# targetboard_v1.net
KiCad netlist of a schematic drawn in EAGLE
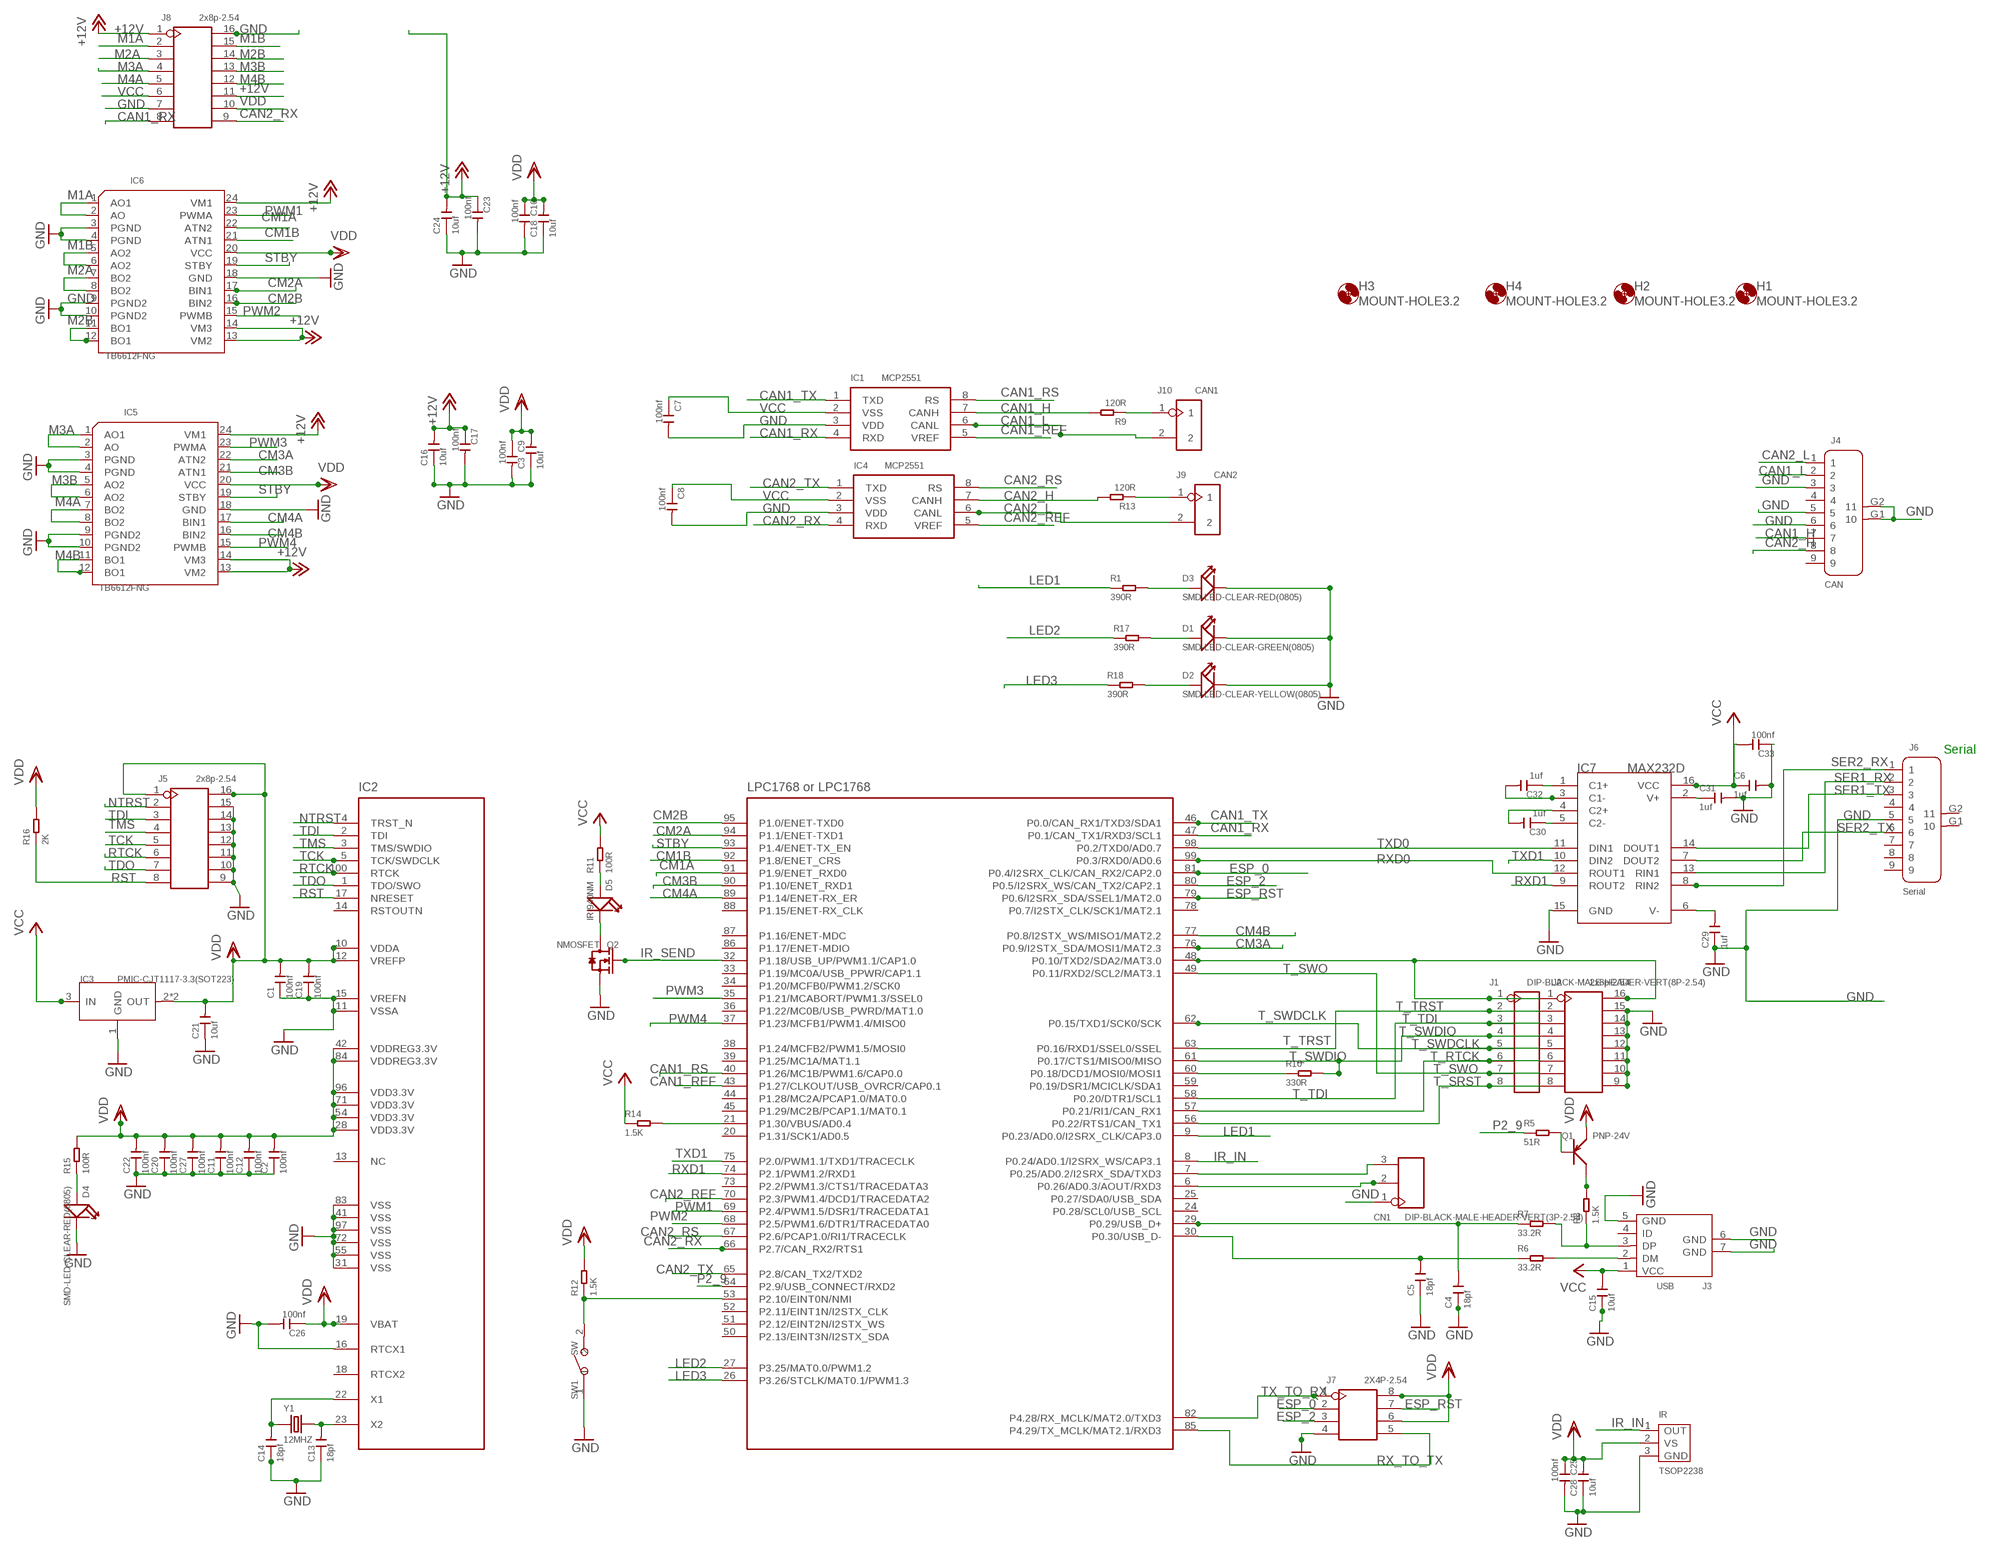
[diagram p0: schematic, sheet 1]

(export (version "E")
  (design (tool "Eeschema 10.0.6"))
  (components
    (comp (ref "C1")
      (value "100nf")
      (footprint "eagle-import:C0805")
      (fields (field (name "MPN") "CC0805KRX7R9BB104"))
      (libsource (lib "eagle-import") (part "CERAMIC-100NF-50V-10%-X7R(0805)"))
    )
    (comp (ref "C2")
      (value "100nf")
      (footprint "eagle-import:C0805")
      (fields (field (name "MPN") "CC0805KRX7R9BB104"))
      (libsource (lib "eagle-import") (part "CERAMIC-100NF-50V-10%-X7R(0805)"))
    )
    (comp (ref "C3")
      (value "10uf")
      (footprint "eagle-import:C0805")
      (fields (field (name "MPN") "CC0805KKX5R8BB106"))
      (libsource (lib "eagle-import") (part "CERAMIC-10UF-25V-10%-X5R(0805)"))
    )
    (comp (ref "C4")
      (value "18pf")
      (footprint "eagle-import:C0805")
      (libsource (lib "eagle-import") (part "CERAMIC-18PF-50V-5%-NPO(0805)"))
    )
    (comp (ref "C5")
      (value "18pf")
      (footprint "eagle-import:C0805")
      (libsource (lib "eagle-import") (part "CERAMIC-18PF-50V-5%-NPO(0805)"))
    )
    (comp (ref "C6")
      (value "1uf")
      (footprint "eagle-import:C0805")
      (fields (field (name "MPN") "CC0805KKX7R8BB105"))
      (libsource (lib "eagle-import") (part "CERAMIC-1UF-25V-10%-X7R(0805)"))
    )
    (comp (ref "C7")
      (value "100nf")
      (footprint "eagle-import:C0805")
      (fields (field (name "MPN") "CC0805KRX7R9BB104"))
      (libsource (lib "eagle-import") (part "CERAMIC-100NF-50V-10%-X7R(0805)"))
    )
    (comp (ref "C8")
      (value "100nf")
      (footprint "eagle-import:C0805")
      (fields (field (name "MPN") "CC0805KRX7R9BB104"))
      (libsource (lib "eagle-import") (part "CERAMIC-100NF-50V-10%-X7R(0805)"))
    )
    (comp (ref "C9")
      (value "100nf")
      (footprint "eagle-import:C0805")
      (fields (field (name "MPN") "CC0805KRX7R9BB104"))
      (libsource (lib "eagle-import") (part "CERAMIC-100NF-50V-10%-X7R(0805)"))
    )
    (comp (ref "C10")
      (value "100nf")
      (footprint "eagle-import:C0805")
      (fields (field (name "MPN") "CC0805KRX7R9BB104"))
      (libsource (lib "eagle-import") (part "CERAMIC-100NF-50V-10%-X7R(0805)"))
    )
    (comp (ref "C11")
      (value "100nf")
      (footprint "eagle-import:C0805")
      (fields (field (name "MPN") "CC0805KRX7R9BB104"))
      (libsource (lib "eagle-import") (part "CERAMIC-100NF-50V-10%-X7R(0805)"))
    )
    (comp (ref "C12")
      (value "100nf")
      (footprint "eagle-import:C0805")
      (fields (field (name "MPN") "CC0805KRX7R9BB104"))
      (libsource (lib "eagle-import") (part "CERAMIC-100NF-50V-10%-X7R(0805)"))
    )
    (comp (ref "C13")
      (value "18pf")
      (footprint "eagle-import:C0805")
      (libsource (lib "eagle-import") (part "CERAMIC-18PF-50V-5%-NPO(0805)"))
    )
    (comp (ref "C14")
      (value "18pf")
      (footprint "eagle-import:C0805")
      (libsource (lib "eagle-import") (part "CERAMIC-18PF-50V-5%-NPO(0805)"))
    )
    (comp (ref "C15")
      (value "10uf")
      (footprint "eagle-import:C0603")
      (fields (field (name "MPN") "CC0603KRX5R6BB106"))
      (libsource (lib "eagle-import") (part "CERAMIC-10UF-10V-10%-X5R(0603)"))
    )
    (comp (ref "C16")
      (value "10uf")
      (footprint "eagle-import:C0805")
      (fields (field (name "MPN") "CC0805KKX5R8BB106"))
      (libsource (lib "eagle-import") (part "CERAMIC-10UF-25V-10%-X5R(0805)"))
    )
    (comp (ref "C17")
      (value "100nf")
      (footprint "eagle-import:C0805")
      (fields (field (name "MPN") "CC0805KRX7R9BB104"))
      (libsource (lib "eagle-import") (part "CERAMIC-100NF-50V-10%-X7R(0805)"))
    )
    (comp (ref "C18")
      (value "10uf")
      (footprint "eagle-import:C0805")
      (fields (field (name "MPN") "CC0805KKX5R8BB106"))
      (libsource (lib "eagle-import") (part "CERAMIC-10UF-25V-10%-X5R(0805)"))
    )
    (comp (ref "C19")
      (value "100nf")
      (footprint "eagle-import:C0805")
      (fields (field (name "MPN") "CC0805KRX7R9BB104"))
      (libsource (lib "eagle-import") (part "CERAMIC-100NF-50V-10%-X7R(0805)"))
    )
    (comp (ref "C20")
      (value "100nf")
      (footprint "eagle-import:C0805")
      (fields (field (name "MPN") "CC0805KRX7R9BB104"))
      (libsource (lib "eagle-import") (part "CERAMIC-100NF-50V-10%-X7R(0805)"))
    )
    (comp (ref "C21")
      (value "10uf")
      (footprint "eagle-import:C0805")
      (fields (field (name "MPN") "CC0805KKX5R8BB106"))
      (libsource (lib "eagle-import") (part "CERAMIC-10UF-25V-10%-X5R(0805)"))
    )
    (comp (ref "C22")
      (value "100nf")
      (footprint "eagle-import:C0805")
      (fields (field (name "MPN") "CC0805KRX7R9BB104"))
      (libsource (lib "eagle-import") (part "CERAMIC-100NF-50V-10%-X7R(0805)"))
    )
    (comp (ref "C23")
      (value "100nf")
      (footprint "eagle-import:C0805")
      (fields (field (name "MPN") "CC0805KRX7R9BB104"))
      (libsource (lib "eagle-import") (part "CERAMIC-100NF-50V-10%-X7R(0805)"))
    )
    (comp (ref "C24")
      (value "10uf")
      (footprint "eagle-import:C0805")
      (fields (field (name "MPN") "CC0805KKX5R8BB106"))
      (libsource (lib "eagle-import") (part "CERAMIC-10UF-25V-10%-X5R(0805)"))
    )
    (comp (ref "C25")
      (value "100nf")
      (footprint "eagle-import:C0805")
      (fields (field (name "MPN") "CC0805KRX7R9BB104"))
      (libsource (lib "eagle-import") (part "CERAMIC-100NF-50V-10%-X7R(0805)"))
    )
    (comp (ref "C26")
      (value "100nf")
      (footprint "eagle-import:C0805")
      (fields (field (name "MPN") "CC0805KRX7R9BB104"))
      (libsource (lib "eagle-import") (part "CERAMIC-100NF-50V-10%-X7R(0805)"))
    )
    (comp (ref "C27")
      (value "100nf")
      (footprint "eagle-import:C0805")
      (fields (field (name "MPN") "CC0805KRX7R9BB104"))
      (libsource (lib "eagle-import") (part "CERAMIC-100NF-50V-10%-X7R(0805)"))
    )
    (comp (ref "C28")
      (value "10uf")
      (footprint "eagle-import:C0805")
      (fields (field (name "MPN") "CC0805KKX5R8BB106"))
      (libsource (lib "eagle-import") (part "CERAMIC-10UF-25V-10%-X5R(0805)"))
    )
    (comp (ref "C29")
      (value "1uf")
      (footprint "eagle-import:C0805")
      (fields (field (name "MPN") "CC0805KKX7R8BB105"))
      (libsource (lib "eagle-import") (part "CERAMIC-1UF-25V-10%-X7R(0805)"))
    )
    (comp (ref "C30")
      (value "1uf")
      (footprint "eagle-import:C0805")
      (fields (field (name "MPN") "CC0805KKX7R8BB105"))
      (libsource (lib "eagle-import") (part "CERAMIC-1UF-25V-10%-X7R(0805)"))
    )
    (comp (ref "C31")
      (value "1uf")
      (footprint "eagle-import:C0805")
      (fields (field (name "MPN") "CC0805KKX7R8BB105"))
      (libsource (lib "eagle-import") (part "CERAMIC-1UF-25V-10%-X7R(0805)"))
    )
    (comp (ref "C32")
      (value "1uf")
      (footprint "eagle-import:C0805")
      (fields (field (name "MPN") "CC0805KKX7R8BB105"))
      (libsource (lib "eagle-import") (part "CERAMIC-1UF-25V-10%-X7R(0805)"))
    )
    (comp (ref "C33")
      (value "100nf")
      (footprint "eagle-import:C0805")
      (fields (field (name "MPN") "CC0805KRX7R9BB104"))
      (libsource (lib "eagle-import") (part "CERAMIC-100NF-50V-10%-X7R(0805)"))
    )
    (comp (ref "CN1")
      (value "DIP-BLACK-MALE-HEADER-VERT(3P-2.54)")
      (footprint "eagle-import:H3-2.54")
      (libsource (lib "eagle-import") (part "DIP-BLACK-MALE-HEADER-VERT(3P-2.54)"))
    )
    (comp (ref "D1")
      (value "SMD-LED-CLEAR-GREEN(0805)")
      (footprint "eagle-import:LED-0805")
      (fields (field (name "MPN") "17-215SYGC/S530-E2/TR8"))
      (libsource (lib "eagle-import") (part "SMD-LED-CLEAR-GREEN(0805)"))
    )
    (comp (ref "D2")
      (value "SMD-LED-CLEAR-YELLOW(0805)")
      (footprint "eagle-import:LED-0805")
      (fields (field (name "MPN") "17-215UYC/S530-A3/TR8"))
      (libsource (lib "eagle-import") (part "SMD-LED-CLEAR-YELLOW(0805)"))
    )
    (comp (ref "D3")
      (value "SMD-LED-CLEAR-RED(0805)")
      (footprint "eagle-import:LED-0805")
      (fields (field (name "MPN") "17-215SURC/S530-A2/TR8"))
      (libsource (lib "eagle-import") (part "SMD-LED-CLEAR-RED(0805)"))
    )
    (comp (ref "D4")
      (value "SMD-LED-CLEAR-RED(0805)")
      (footprint "eagle-import:LED-0805")
      (fields (field (name "MPN") "17-215SURC/S530-A2/TR8"))
      (libsource (lib "eagle-import") (part "SMD-LED-CLEAR-RED(0805)"))
    )
    (comp (ref "D5")
      (value "IR 940NM")
      (footprint "eagle-import:LED2-2.54-D5.0MM")
      (fields (field (name "MPN") "IR523B-W60W1"))
      (libsource (lib "eagle-import") (part "DIP-IR-LED-940NM(2P-D5MM)"))
    )
    (comp (ref "H1")
      (value "MOUNT-HOLE3.2")
      (footprint "eagle-import:3,2")
      (libsource (lib "eagle-import") (part "MOUNT-HOLE3.2"))
    )
    (comp (ref "H2")
      (value "MOUNT-HOLE3.2")
      (footprint "eagle-import:3,2")
      (libsource (lib "eagle-import") (part "MOUNT-HOLE3.2"))
    )
    (comp (ref "H3")
      (value "MOUNT-HOLE3.2")
      (footprint "eagle-import:3,2")
      (libsource (lib "eagle-import") (part "MOUNT-HOLE3.2"))
    )
    (comp (ref "H4")
      (value "MOUNT-HOLE3.2")
      (footprint "eagle-import:3,2")
      (libsource (lib "eagle-import") (part "MOUNT-HOLE3.2"))
    )
    (comp (ref "IC1")
      (value "MCP2551")
      (footprint "eagle-import:SOIC8-1.27-5X4MM")
      (fields (field (name "MPN") "MCP2551-I/SN"))
      (libsource (lib "eagle-import") (part "INTERFACE-MCP2551-I/SN(SOIC8)"))
    )
    (comp (ref "IC2")
      (value "LPC1768 or LPC1768")
      (footprint "eagle-import:LQFP100-0.5-13.8X13.8MM")
      (fields (field (name "MPN") "LPC1768FBD100"))
      (libsource (lib "eagle-import") (part "MCU_LPC1768FBD100(LQFP100)"))
    )
    (comp (ref "IC3")
      (value "PMIC-CJT1117-3.3(SOT223)")
      (footprint "eagle-import:SOT-223")
      (fields (field (name "MPN") "CJT1117-3.3"))
      (libsource (lib "eagle-import") (part "PMIC-CJT1117-3.3(SOT223)"))
    )
    (comp (ref "IC4")
      (value "MCP2551")
      (footprint "eagle-import:SOIC8-1.27-5X4MM")
      (fields (field (name "MPN") "MCP2551-I/SN"))
      (libsource (lib "eagle-import") (part "INTERFACE-MCP2551-I/SN(SOIC8)"))
    )
    (comp (ref "IC5")
      (value "TB6612FNG")
      (footprint "eagle-import:SSOP24-0.65-8.9X5.3MM")
      (fields (field (name "MPN") "TB6612FNG-O/C8/EL"))
      (libsource (lib "eagle-import") (part "DRIVER-TB6612FNG-O/C8/EL(SSOP24)"))
    )
    (comp (ref "IC6")
      (value "TB6612FNG")
      (footprint "eagle-import:SSOP24-0.65-8.9X5.3MM")
      (fields (field (name "MPN") "TB6612FNG-O/C8/EL"))
      (libsource (lib "eagle-import") (part "DRIVER-TB6612FNG-O/C8/EL(SSOP24)"))
    )
    (comp (ref "IC7")
      (value "MAX232D")
      (footprint "eagle-import:SOIC16-1.27-10X3.9MM")
      (libsource (lib "eagle-import") (part "RECEIVER-MAX232D(SOIC16)"))
    )
    (comp (ref "IR")
      (value "TSOP2238")
      (footprint "eagle-import:SNR3-2.54-6.95X6.0X5.6MM")
      (libsource (lib "eagle-import") (part "OPTICAL-TSOP2238"))
    )
    (comp (ref "J1")
      (value "DIP-BLACK-MALE-HEADER-VERT(8P-2.54)")
      (footprint "eagle-import:H8-2.54")
      (fields (field (name "MPN") "P125-1108A1BS116A1"))
      (libsource (lib "eagle-import") (part "DIP-BLACK-MALE-HEADER-VERT(8P-2.54)"))
    )
    (comp (ref "J2")
      (value "2x8p-2.54")
      (footprint "eagle-import:H2X8-2.54")
      (fields (field (name "MPN") "P125-1216A0AS116A1"))
      (libsource (lib "eagle-import") (part "DIP-BLACK-MALE-HEADER-VERT(2X8P-2.54)"))
    )
    (comp (ref "J3")
      (value "USB")
      (footprint "eagle-import:MICRO-USB5+2P-SMD-0.65")
      (fields (field (name "MPN") "ST-USB-001L"))
      (libsource (lib "eagle-import") (part "MICRO-USB-SMD-TYPE-AB-R/A(ST-USB-001L)"))
    )
    (comp (ref "J4")
      (value "CAN")
      (footprint "eagle-import:DSUB9+2P-2.77-90D-MALE")
      (libsource (lib "eagle-import") (part "DIP-MALE-DB9-CONNECTOR"))
    )
    (comp (ref "J5")
      (value "2x8p-2.54")
      (footprint "eagle-import:H2X8-2.54")
      (fields (field (name "MPN") "P125-1216A0AS116A1"))
      (libsource (lib "eagle-import") (part "DIP-BLACK-MALE-HEADER-VERT(2X8P-2.54)"))
    )
    (comp (ref "J6")
      (value "Serial")
      (footprint "eagle-import:DSUB9+2P-2.77-90D-MALE")
      (libsource (lib "eagle-import") (part "DIP-MALE-DB9-CONNECTOR"))
    )
    (comp (ref "J7")
      (value "2X4P-2.54")
      (footprint "eagle-import:H2X4-2.54")
      (libsource (lib "eagle-import") (part "DIP-BLACK-FEMALE-HEADER(2X4P-2.54)"))
    )
    (comp (ref "J8")
      (value "2x8p-2.54")
      (footprint "eagle-import:H2X8-2.54")
      (fields (field (name "MPN") "P125-1216A0AS116A1"))
      (libsource (lib "eagle-import") (part "DIP-BLACK-MALE-HEADER-VERT(2X8P-2.54)"))
    )
    (comp (ref "J9")
      (value "CAN2")
      (footprint "eagle-import:H2-2.54")
      (fields (field (name "MPN") "P125-1102A0BS116A3"))
      (libsource (lib "eagle-import") (part "DIP-WHITE-MALE-HEADER-VERT(2P-2.54)"))
    )
    (comp (ref "J10")
      (value "CAN1")
      (footprint "eagle-import:H2-2.54")
      (fields (field (name "MPN") "P125-1102A0BS116A3"))
      (libsource (lib "eagle-import") (part "DIP-WHITE-MALE-HEADER-VERT(2P-2.54)"))
    )
    (comp (ref "Q1")
      (value "PNP-24V")
      (footprint "eagle-import:SOT-23")
      (fields (field (name "MPN") "S8550"))
      (libsource (lib "eagle-import") (part "SMD-TRANSISTORS-PNP-25V-500MA(SOT-23)"))
    )
    (comp (ref "Q2")
      (value "NMOSFET")
      (footprint "eagle-import:SOT-23")
      (fields (field (name "MPN") "2N7002,215"))
      (libsource (lib "eagle-import") (part "SMD-MOSFET-N-CH-60V-300MA-LOGIC-LEVEL-FET(SOT-23)"))
    )
    (comp (ref "R1")
      (value "390R")
      (footprint "eagle-import:R0805")
      (fields (field (name "MPN") "RC0805JR-07390RL"))
      (libsource (lib "eagle-import") (part "SMD-RES-390R-5%-1/8W(0805)"))
    )
    (comp (ref "R5")
      (value "51R")
      (footprint "eagle-import:R0603")
      (fields (field (name "MPN") "RC0603FR-0751RL"))
      (libsource (lib "eagle-import") (part "SMD-RES-51R-1%-1/10W(0603)"))
    )
    (comp (ref "R6")
      (value "33.2R")
      (footprint "eagle-import:R0603")
      (fields (field (name "MPN") "RC0603FR-0733R2L"))
      (libsource (lib "eagle-import") (part "SMD-RES-33.2R-1%-1/10W(0603)"))
    )
    (comp (ref "R7")
      (value "33.2R")
      (footprint "eagle-import:R0603")
      (fields (field (name "MPN") "RC0603FR-0733R2L"))
      (libsource (lib "eagle-import") (part "SMD-RES-33.2R-1%-1/10W(0603)"))
    )
    (comp (ref "R8")
      (value "1.5K")
      (footprint "eagle-import:R0805")
      (fields (field (name "MPN") "RC0805FR-071K5L"))
      (libsource (lib "eagle-import") (part "SMD-RES-1.5K-1%-1/8W(0805)"))
    )
    (comp (ref "R9")
      (value "120R")
      (footprint "eagle-import:R0805")
      (fields (field (name "MPN") "RC0805JR-07120RL"))
      (libsource (lib "eagle-import") (part "SMD-RES-120R-5%-1/8W(0805)"))
    )
    (comp (ref "R10")
      (value "330R")
      (footprint "eagle-import:R0603")
      (fields (field (name "MPN") "RC0603FR-07330RL"))
      (libsource (lib "eagle-import") (part "SMD-RES-330R-1%-1/10W(0603)"))
    )
    (comp (ref "R11")
      (value "100R")
      (footprint "eagle-import:R0805")
      (fields (field (name "MPN") "RC0805JR-07100RL"))
      (libsource (lib "eagle-import") (part "SMD-RES-100R-5%-1/8W(0805)"))
    )
    (comp (ref "R12")
      (value "1.5K")
      (footprint "eagle-import:R0805")
      (fields (field (name "MPN") "RC0805FR-071K5L"))
      (libsource (lib "eagle-import") (part "SMD-RES-1.5K-1%-1/8W(0805)"))
    )
    (comp (ref "R13")
      (value "120R")
      (footprint "eagle-import:R0805")
      (fields (field (name "MPN") "RC0805JR-07120RL"))
      (libsource (lib "eagle-import") (part "SMD-RES-120R-5%-1/8W(0805)"))
    )
    (comp (ref "R14")
      (value "1.5K")
      (footprint "eagle-import:R0805")
      (fields (field (name "MPN") "RC0805FR-071K5L"))
      (libsource (lib "eagle-import") (part "SMD-RES-1.5K-1%-1/8W(0805)"))
    )
    (comp (ref "R15")
      (value "100R")
      (footprint "eagle-import:R0805")
      (fields (field (name "MPN") "RC0805JR-07100RL"))
      (libsource (lib "eagle-import") (part "SMD-RES-100R-5%-1/8W(0805)"))
    )
    (comp (ref "R16")
      (value "2K")
      (footprint "eagle-import:R0805")
      (fields (field (name "MPN") "RC0805JR-072KL"))
      (libsource (lib "eagle-import") (part "SMD-RES-2K-5%-1/8W(0805)"))
    )
    (comp (ref "R17")
      (value "390R")
      (footprint "eagle-import:R0805")
      (fields (field (name "MPN") "RC0805JR-07390RL"))
      (libsource (lib "eagle-import") (part "SMD-RES-390R-5%-1/8W(0805)"))
    )
    (comp (ref "R18")
      (value "390R")
      (footprint "eagle-import:R0805")
      (fields (field (name "MPN") "RC0805JR-07390RL"))
      (libsource (lib "eagle-import") (part "SMD-RES-390R-5%-1/8W(0805)"))
    )
    (comp (ref "SW1")
      (value "SW")
      (footprint "eagle-import:SW2-2.6-3.0X2.5X1.2+0.4MM")
      (libsource (lib "eagle-import") (part "SMD-BUTTON(2P-3.0X2.5X1.2+0.4MM)-B3U-1000P-2P-SMD"))
    )
    (comp (ref "Y1")
      (value "12MHZ")
      (footprint "eagle-import:X2-SMD-5.0X3.2X1.3MM")
      (fields (field (name "MPN") "5032/2P"))
      (libsource (lib "eagle-import") (part "SMD-CRYSTAL-12MHZ-20PF-20PPM-40R(2P-5.0X3.2MM)"))
    )
  )
  (nets
    (net (code "1") (name "+12V") (class "Default")
      (node (ref "C16") (pin "2") (pinfunction "2_2") (pintype "passive"))
      (node (ref "C17") (pin "1") (pinfunction "1_1") (pintype "passive"))
      (node (ref "C23") (pin "1") (pinfunction "1_1") (pintype "passive"))
      (node (ref "C24") (pin "2") (pinfunction "2_2") (pintype "passive"))
      (node (ref "IC5") (pin "13") (pinfunction "VM2_13") (pintype "bidirectional"))
      (node (ref "IC5") (pin "14") (pinfunction "VM3_14") (pintype "bidirectional"))
      (node (ref "IC5") (pin "24") (pinfunction "VM1_24") (pintype "bidirectional"))
      (node (ref "IC6") (pin "13") (pinfunction "VM2_13") (pintype "bidirectional"))
      (node (ref "IC6") (pin "14") (pinfunction "VM3_14") (pintype "bidirectional"))
      (node (ref "IC6") (pin "24") (pinfunction "VM1_24") (pintype "bidirectional"))
      (node (ref "J8") (pin "1") (pinfunction "1_1") (pintype "bidirectional"))
      (node (ref "J8") (pin "11") (pinfunction "11_11") (pintype "bidirectional"))
    )
    (net (code "2") (name "/CAN1_H") (class "Default")
      (node (ref "IC1") (pin "7") (pinfunction "CANH_7") (pintype "bidirectional"))
      (node (ref "J4") (pin "7") (pinfunction "7_7") (pintype "bidirectional"))
      (node (ref "R9") (pin "2") (pinfunction "2_2") (pintype "passive"))
    )
    (net (code "3") (name "/CAN1_L") (class "Default")
      (node (ref "IC1") (pin "6") (pinfunction "CANL_6") (pintype "bidirectional"))
      (node (ref "J10") (pin "2") (pinfunction "2_2") (pintype "bidirectional"))
      (node (ref "J4") (pin "2") (pinfunction "2_2") (pintype "bidirectional"))
    )
    (net (code "4") (name "/CAN1_REF") (class "Default")
      (node (ref "IC1") (pin "5") (pinfunction "VREF_5") (pintype "bidirectional"))
      (node (ref "IC2") (pin "43") (pinfunction "P1.27/CLKOUT/USB_OVRCR/CAP0.1_43") (pintype "bidirectional"))
    )
    (net (code "5") (name "/CAN1_RS") (class "Default")
      (node (ref "IC1") (pin "8") (pinfunction "RS_8") (pintype "bidirectional"))
      (node (ref "IC2") (pin "40") (pinfunction "P1.26/MC1B/PWM1.6/CAP0.0_40") (pintype "bidirectional"))
    )
    (net (code "6") (name "/CAN1_RX") (class "Default")
      (node (ref "IC1") (pin "4") (pinfunction "RXD_4") (pintype "bidirectional"))
      (node (ref "IC2") (pin "47") (pinfunction "P0.1/CAN_TX1/RXD3/SCL1_47") (pintype "bidirectional"))
      (node (ref "J8") (pin "8") (pinfunction "8_8") (pintype "bidirectional"))
    )
    (net (code "7") (name "/CAN1_TX") (class "Default")
      (node (ref "IC1") (pin "1") (pinfunction "TXD_1") (pintype "bidirectional"))
      (node (ref "IC2") (pin "46") (pinfunction "P0.0/CAN_RX1/TXD3/SDA1_46") (pintype "bidirectional"))
    )
    (net (code "8") (name "/CAN2_H") (class "Default")
      (node (ref "IC4") (pin "7") (pinfunction "CANH_7") (pintype "bidirectional"))
      (node (ref "J4") (pin "8") (pinfunction "8_8") (pintype "bidirectional"))
      (node (ref "R13") (pin "2") (pinfunction "2_2") (pintype "passive"))
    )
    (net (code "9") (name "/CAN2_L") (class "Default")
      (node (ref "IC4") (pin "6") (pinfunction "CANL_6") (pintype "bidirectional"))
      (node (ref "J4") (pin "1") (pinfunction "1_1") (pintype "bidirectional"))
      (node (ref "J9") (pin "2") (pinfunction "2_2") (pintype "bidirectional"))
    )
    (net (code "10") (name "/CAN2_REF") (class "Default")
      (node (ref "IC2") (pin "70") (pinfunction "P2.3/PWM1.4/DCD1/TRACEDATA2_70") (pintype "bidirectional"))
      (node (ref "IC4") (pin "5") (pinfunction "VREF_5") (pintype "bidirectional"))
    )
    (net (code "11") (name "/CAN2_RS") (class "Default")
      (node (ref "IC2") (pin "67") (pinfunction "P2.6/PCAP1.0/RI1/TRACECLK_67") (pintype "bidirectional"))
      (node (ref "IC4") (pin "8") (pinfunction "RS_8") (pintype "bidirectional"))
    )
    (net (code "12") (name "/CAN2_RX") (class "Default")
      (node (ref "IC2") (pin "66") (pinfunction "P2.7/CAN_RX2/RTS1_66") (pintype "bidirectional"))
      (node (ref "IC4") (pin "4") (pinfunction "RXD_4") (pintype "bidirectional"))
      (node (ref "J8") (pin "9") (pinfunction "9_9") (pintype "bidirectional"))
    )
    (net (code "13") (name "/CAN2_TX") (class "Default")
      (node (ref "IC2") (pin "65") (pinfunction "P2.8/CAN_TX2/TXD2_65") (pintype "bidirectional"))
      (node (ref "IC4") (pin "1") (pinfunction "TXD_1") (pintype "bidirectional"))
    )
    (net (code "14") (name "/CM1A") (class "Default")
      (node (ref "IC2") (pin "91") (pinfunction "P1.9/ENET_RXD0_91") (pintype "bidirectional"))
      (node (ref "IC6") (pin "22") (pinfunction "ATN2_22") (pintype "bidirectional"))
    )
    (net (code "15") (name "/CM1B") (class "Default")
      (node (ref "IC2") (pin "92") (pinfunction "P1.8/ENET_CRS_92") (pintype "bidirectional"))
      (node (ref "IC6") (pin "21") (pinfunction "ATN1_21") (pintype "bidirectional"))
    )
    (net (code "16") (name "/CM2A") (class "Default")
      (node (ref "IC2") (pin "94") (pinfunction "P1.1/ENET-TXD1_94") (pintype "bidirectional"))
      (node (ref "IC6") (pin "17") (pinfunction "BIN1_17") (pintype "bidirectional"))
    )
    (net (code "17") (name "/CM2B") (class "Default")
      (node (ref "IC2") (pin "95") (pinfunction "P1.0/ENET-TXD0_95") (pintype "bidirectional"))
      (node (ref "IC6") (pin "16") (pinfunction "BIN2_16") (pintype "bidirectional"))
    )
    (net (code "18") (name "/CM3A") (class "Default")
      (node (ref "IC2") (pin "76") (pinfunction "P0.9/I2STX_SDA/MOSI1/MAT2.3_76") (pintype "bidirectional"))
      (node (ref "IC5") (pin "22") (pinfunction "ATN2_22") (pintype "bidirectional"))
    )
    (net (code "19") (name "/CM3B") (class "Default")
      (node (ref "IC2") (pin "90") (pinfunction "P1.10/ENET_RXD1_90") (pintype "bidirectional"))
      (node (ref "IC5") (pin "21") (pinfunction "ATN1_21") (pintype "bidirectional"))
    )
    (net (code "20") (name "/CM4A") (class "Default")
      (node (ref "IC2") (pin "89") (pinfunction "P1.14/ENET-RX_ER_89") (pintype "bidirectional"))
      (node (ref "IC5") (pin "17") (pinfunction "BIN1_17") (pintype "bidirectional"))
    )
    (net (code "21") (name "/CM4B") (class "Default")
      (node (ref "IC2") (pin "77") (pinfunction "P0.8/I2STX_WS/MISO1/MAT2.2_77") (pintype "bidirectional"))
      (node (ref "IC5") (pin "16") (pinfunction "BIN2_16") (pintype "bidirectional"))
    )
    (net (code "22") (name "/ESP_0") (class "Default")
      (node (ref "IC2") (pin "81") (pinfunction "P0.4/I2SRX_CLK/CAN_RX2/CAP2.0_81") (pintype "bidirectional"))
      (node (ref "J7") (pin "2") (pinfunction "2_2") (pintype "bidirectional"))
    )
    (net (code "23") (name "/ESP_2") (class "Default")
      (node (ref "IC2") (pin "80") (pinfunction "P0.5/I2SRX_WS/CAN_TX2/CAP2.1_80") (pintype "bidirectional"))
      (node (ref "J7") (pin "3") (pinfunction "3_3") (pintype "bidirectional"))
    )
    (net (code "24") (name "/ESP_RST") (class "Default")
      (node (ref "IC2") (pin "79") (pinfunction "P0.6/I2SRX_SDA/SSEL1/MAT2.0_79") (pintype "bidirectional"))
      (node (ref "J7") (pin "7") (pinfunction "7_7") (pintype "bidirectional"))
    )
    (net (code "25") (name "/IR_IN") (class "Default")
      (node (ref "IC2") (pin "8") (pinfunction "P0.24/AD0.1/I2SRX_WS/CAP3.1_8") (pintype "bidirectional"))
      (node (ref "IR") (pin "1") (pinfunction "OUT_1") (pintype "bidirectional"))
    )
    (net (code "26") (name "/IR_SEND") (class "Default")
      (node (ref "IC2") (pin "32") (pinfunction "P1.18/USB_UP/PWM1.1/CAP1.0_32") (pintype "bidirectional"))
      (node (ref "Q2") (pin "1") (pinfunction "G_1") (pintype "passive"))
    )
    (net (code "27") (name "/LED1") (class "Default")
      (node (ref "IC2") (pin "9") (pinfunction "P0.23/AD0.0/I2SRX_CLK/CAP3.0_9") (pintype "bidirectional"))
      (node (ref "R1") (pin "1") (pinfunction "1_1") (pintype "passive"))
    )
    (net (code "28") (name "/LED2") (class "Default")
      (node (ref "IC2") (pin "27") (pinfunction "P3.25/MAT0.0/PWM1.2_27") (pintype "bidirectional"))
      (node (ref "R17") (pin "1") (pinfunction "1_1") (pintype "passive"))
    )
    (net (code "29") (name "/LED3") (class "Default")
      (node (ref "IC2") (pin "26") (pinfunction "P3.26/STCLK/MAT0.1/PWM1.3_26") (pintype "bidirectional"))
      (node (ref "R18") (pin "1") (pinfunction "1_1") (pintype "passive"))
    )
    (net (code "30") (name "/M1A") (class "Default")
      (node (ref "IC6") (pin "1") (pinfunction "AO1_1") (pintype "bidirectional"))
      (node (ref "IC6") (pin "2") (pinfunction "AO_2") (pintype "bidirectional"))
      (node (ref "J8") (pin "2") (pinfunction "2_2") (pintype "bidirectional"))
    )
    (net (code "31") (name "/M1B") (class "Default")
      (node (ref "IC6") (pin "5") (pinfunction "AO2_5") (pintype "bidirectional"))
      (node (ref "IC6") (pin "6") (pinfunction "AO2_6") (pintype "bidirectional"))
      (node (ref "J8") (pin "15") (pinfunction "15_15") (pintype "bidirectional"))
    )
    (net (code "32") (name "/M2A") (class "Default")
      (node (ref "IC6") (pin "7") (pinfunction "BO2_7") (pintype "bidirectional"))
      (node (ref "IC6") (pin "8") (pinfunction "BO2_8") (pintype "bidirectional"))
      (node (ref "J8") (pin "3") (pinfunction "3_3") (pintype "bidirectional"))
    )
    (net (code "33") (name "/M2B") (class "Default")
      (node (ref "IC6") (pin "11") (pinfunction "BO1_11") (pintype "bidirectional"))
      (node (ref "IC6") (pin "12") (pinfunction "BO1_12") (pintype "bidirectional"))
      (node (ref "J8") (pin "14") (pinfunction "14_14") (pintype "bidirectional"))
    )
    (net (code "34") (name "/M3A") (class "Default")
      (node (ref "IC5") (pin "1") (pinfunction "AO1_1") (pintype "bidirectional"))
      (node (ref "IC5") (pin "2") (pinfunction "AO_2") (pintype "bidirectional"))
      (node (ref "J8") (pin "4") (pinfunction "4_4") (pintype "bidirectional"))
    )
    (net (code "35") (name "/M3B") (class "Default")
      (node (ref "IC5") (pin "5") (pinfunction "AO2_5") (pintype "bidirectional"))
      (node (ref "IC5") (pin "6") (pinfunction "AO2_6") (pintype "bidirectional"))
      (node (ref "J8") (pin "13") (pinfunction "13_13") (pintype "bidirectional"))
    )
    (net (code "36") (name "/M4A") (class "Default")
      (node (ref "IC5") (pin "7") (pinfunction "BO2_7") (pintype "bidirectional"))
      (node (ref "IC5") (pin "8") (pinfunction "BO2_8") (pintype "bidirectional"))
      (node (ref "J8") (pin "5") (pinfunction "5_5") (pintype "bidirectional"))
    )
    (net (code "37") (name "/M4B") (class "Default")
      (node (ref "IC5") (pin "11") (pinfunction "BO1_11") (pintype "bidirectional"))
      (node (ref "IC5") (pin "12") (pinfunction "BO1_12") (pintype "bidirectional"))
      (node (ref "J8") (pin "12") (pinfunction "12_12") (pintype "bidirectional"))
    )
    (net (code "38") (name "/NTRST") (class "Default")
      (node (ref "IC2") (pin "4") (pinfunction "TRST_N_4") (pintype "bidirectional"))
      (node (ref "J5") (pin "2") (pinfunction "2_2") (pintype "bidirectional"))
    )
    (net (code "39") (name "/P2_9") (class "Default")
      (node (ref "IC2") (pin "64") (pinfunction "P2.9/USB_CONNECT/RXD2_64") (pintype "bidirectional"))
      (node (ref "R5") (pin "1") (pinfunction "1_1") (pintype "passive"))
    )
    (net (code "40") (name "/PWM1") (class "Default")
      (node (ref "IC2") (pin "69") (pinfunction "P2.4/PWM1.5/DSR1/TRACEDATA1_69") (pintype "bidirectional"))
      (node (ref "IC6") (pin "23") (pinfunction "PWMA_23") (pintype "bidirectional"))
    )
    (net (code "41") (name "/PWM2") (class "Default")
      (node (ref "IC2") (pin "68") (pinfunction "P2.5/PWM1.6/DTR1/TRACEDATA0_68") (pintype "bidirectional"))
      (node (ref "IC6") (pin "15") (pinfunction "PWMB_15") (pintype "bidirectional"))
    )
    (net (code "42") (name "/PWM3") (class "Default")
      (node (ref "IC2") (pin "35") (pinfunction "P1.21/MCABORT/PWM1.3/SSEL0_35") (pintype "bidirectional"))
      (node (ref "IC5") (pin "23") (pinfunction "PWMA_23") (pintype "bidirectional"))
    )
    (net (code "43") (name "/PWM4") (class "Default")
      (node (ref "IC2") (pin "37") (pinfunction "P1.23/MCFB1/PWM1.4/MISO0_37") (pintype "bidirectional"))
      (node (ref "IC5") (pin "15") (pinfunction "PWMB_15") (pintype "bidirectional"))
    )
    (net (code "44") (name "/RST") (class "Default")
      (node (ref "IC2") (pin "17") (pinfunction "NRESET_17") (pintype "bidirectional"))
      (node (ref "J5") (pin "8") (pinfunction "8_8") (pintype "bidirectional"))
      (node (ref "R16") (pin "1") (pinfunction "1_1") (pintype "passive"))
    )
    (net (code "45") (name "/RTCK") (class "Default")
      (node (ref "IC2") (pin "100") (pinfunction "RTCK_100") (pintype "bidirectional"))
      (node (ref "J5") (pin "6") (pinfunction "6_6") (pintype "bidirectional"))
    )
    (net (code "46") (name "/RXD0") (class "Default")
      (node (ref "IC2") (pin "99") (pinfunction "P0.3/RXD0/AD0.6_99") (pintype "bidirectional"))
      (node (ref "IC7") (pin "12") (pinfunction "ROUT1_12") (pintype "bidirectional"))
    )
    (net (code "47") (name "/RXD1") (class "Default")
      (node (ref "IC2") (pin "74") (pinfunction "P2.1/PWM1.2/RXD1_74") (pintype "bidirectional"))
      (node (ref "IC7") (pin "9") (pinfunction "ROUT2_9") (pintype "bidirectional"))
    )
    (net (code "48") (name "/RX_TO_TX") (class "Default")
      (node (ref "IC2") (pin "85") (pinfunction "P4.29/TX_MCLK/MAT2.1/RXD3_85") (pintype "bidirectional"))
      (node (ref "J7") (pin "5") (pinfunction "5_5") (pintype "bidirectional"))
    )
    (net (code "49") (name "/SER1_RX") (class "Default")
      (node (ref "IC7") (pin "13") (pinfunction "RIN1_13") (pintype "bidirectional"))
      (node (ref "J6") (pin "2") (pinfunction "2_2") (pintype "bidirectional"))
    )
    (net (code "50") (name "/SER1_TX") (class "Default")
      (node (ref "IC7") (pin "14") (pinfunction "DOUT1_14") (pintype "bidirectional"))
      (node (ref "J6") (pin "3") (pinfunction "3_3") (pintype "bidirectional"))
    )
    (net (code "51") (name "/SER2_RX") (class "Default")
      (node (ref "IC7") (pin "8") (pinfunction "RIN2_8") (pintype "bidirectional"))
      (node (ref "J6") (pin "1") (pinfunction "1_1") (pintype "bidirectional"))
    )
    (net (code "52") (name "/SER2_TX") (class "Default")
      (node (ref "IC7") (pin "7") (pinfunction "DOUT2_7") (pintype "bidirectional"))
      (node (ref "J6") (pin "6") (pinfunction "6_6") (pintype "bidirectional"))
    )
    (net (code "53") (name "/STBY") (class "Default")
      (node (ref "IC2") (pin "93") (pinfunction "P1.4/ENET-TX_EN_93") (pintype "bidirectional"))
      (node (ref "IC5") (pin "19") (pinfunction "STBY_19") (pintype "bidirectional"))
      (node (ref "IC6") (pin "19") (pinfunction "STBY_19") (pintype "bidirectional"))
    )
    (net (code "54") (name "/TCK") (class "Default")
      (node (ref "IC2") (pin "5") (pinfunction "TCK/SWDCLK_5") (pintype "bidirectional"))
      (node (ref "J5") (pin "5") (pinfunction "5_5") (pintype "bidirectional"))
    )
    (net (code "55") (name "/TDI") (class "Default")
      (node (ref "IC2") (pin "2") (pinfunction "TDI_2") (pintype "bidirectional"))
      (node (ref "J5") (pin "3") (pinfunction "3_3") (pintype "bidirectional"))
    )
    (net (code "56") (name "/TDO") (class "Default")
      (node (ref "IC2") (pin "1") (pinfunction "TDO/SWO_1") (pintype "bidirectional"))
      (node (ref "J5") (pin "7") (pinfunction "7_7") (pintype "bidirectional"))
    )
    (net (code "57") (name "/TMS") (class "Default")
      (node (ref "IC2") (pin "3") (pinfunction "TMS/SWDIO_3") (pintype "bidirectional"))
      (node (ref "J5") (pin "4") (pinfunction "4_4") (pintype "bidirectional"))
    )
    (net (code "58") (name "/TXD0") (class "Default")
      (node (ref "IC2") (pin "98") (pinfunction "P0.2/TXD0/AD0.7_98") (pintype "bidirectional"))
      (node (ref "IC7") (pin "11") (pinfunction "DIN1_11") (pintype "input"))
    )
    (net (code "59") (name "/TXD1") (class "Default")
      (node (ref "IC2") (pin "75") (pinfunction "P2.0/PWM1.1/TXD1/TRACECLK_75") (pintype "bidirectional"))
      (node (ref "IC7") (pin "10") (pinfunction "DIN2_10") (pintype "bidirectional"))
    )
    (net (code "60") (name "/TX_TO_RX") (class "Default")
      (node (ref "IC2") (pin "82") (pinfunction "P4.28/RX_MCLK/MAT2.0/TXD3_82") (pintype "bidirectional"))
      (node (ref "J7") (pin "1") (pinfunction "1_1") (pintype "bidirectional"))
    )
    (net (code "61") (name "/T_RTCK") (class "Default")
      (node (ref "IC2") (pin "57") (pinfunction "P0.21/RI1/CAN_RX1_57") (pintype "bidirectional"))
      (node (ref "J1") (pin "6") (pinfunction "6_6") (pintype "bidirectional"))
      (node (ref "J2") (pin "6") (pinfunction "6_6") (pintype "bidirectional"))
    )
    (net (code "62") (name "/T_SRST") (class "Default")
      (node (ref "IC2") (pin "56") (pinfunction "P0.22/RTS1/CAN_TX1_56") (pintype "bidirectional"))
      (node (ref "J1") (pin "8") (pinfunction "8_8") (pintype "bidirectional"))
      (node (ref "J2") (pin "8") (pinfunction "8_8") (pintype "bidirectional"))
    )
    (net (code "63") (name "/T_SWDCLK") (class "Default")
      (node (ref "IC2") (pin "62") (pinfunction "P0.15/TXD1/SCK0/SCK_62") (pintype "bidirectional"))
      (node (ref "J1") (pin "5") (pinfunction "5_5") (pintype "bidirectional"))
      (node (ref "J2") (pin "5") (pinfunction "5_5") (pintype "bidirectional"))
    )
    (net (code "64") (name "/T_SWDIO") (class "Default")
      (node (ref "IC2") (pin "61") (pinfunction "P0.17/CTS1/MISO0/MISO_61") (pintype "bidirectional"))
      (node (ref "J1") (pin "4") (pinfunction "4_4") (pintype "bidirectional"))
      (node (ref "J2") (pin "4") (pinfunction "4_4") (pintype "bidirectional"))
      (node (ref "R10") (pin "2") (pinfunction "2_2") (pintype "passive"))
    )
    (net (code "65") (name "/T_SWO") (class "Default")
      (node (ref "IC2") (pin "49") (pinfunction "P0.11/RXD2/SCL2/MAT3.1_49") (pintype "bidirectional"))
      (node (ref "J1") (pin "7") (pinfunction "7_7") (pintype "bidirectional"))
      (node (ref "J2") (pin "7") (pinfunction "7_7") (pintype "bidirectional"))
    )
    (net (code "66") (name "/T_TDI") (class "Default")
      (node (ref "IC2") (pin "58") (pinfunction "P0.20/DTR1/SCL1_58") (pintype "bidirectional"))
      (node (ref "J1") (pin "3") (pinfunction "3_3") (pintype "bidirectional"))
      (node (ref "J2") (pin "3") (pinfunction "3_3") (pintype "bidirectional"))
    )
    (net (code "67") (name "/T_TRST") (class "Default")
      (node (ref "IC2") (pin "63") (pinfunction "P0.16/RXD1/SSEL0/SSEL_63") (pintype "bidirectional"))
      (node (ref "J1") (pin "2") (pinfunction "2_2") (pintype "bidirectional"))
      (node (ref "J2") (pin "2") (pinfunction "2_2") (pintype "bidirectional"))
    )
    (net (code "68") (name "GND") (class "Default")
      (node (ref "C1") (pin "1") (pinfunction "1_1") (pintype "passive"))
      (node (ref "C10") (pin "2") (pinfunction "2_2") (pintype "passive"))
      (node (ref "C11") (pin "1") (pinfunction "1_1") (pintype "passive"))
      (node (ref "C12") (pin "1") (pinfunction "1_1") (pintype "passive"))
      (node (ref "C13") (pin "1") (pinfunction "1_1") (pintype "passive"))
      (node (ref "C14") (pin "1") (pinfunction "1_1") (pintype "passive"))
      (node (ref "C15") (pin "1") (pinfunction "1_1") (pintype "passive"))
      (node (ref "C16") (pin "1") (pinfunction "1_1") (pintype "passive"))
      (node (ref "C17") (pin "2") (pinfunction "2_2") (pintype "passive"))
      (node (ref "C18") (pin "1") (pinfunction "1_1") (pintype "passive"))
      (node (ref "C19") (pin "1") (pinfunction "1_1") (pintype "passive"))
      (node (ref "C2") (pin "1") (pinfunction "1_1") (pintype "passive"))
      (node (ref "C20") (pin "1") (pinfunction "1_1") (pintype "passive"))
      (node (ref "C21") (pin "1") (pinfunction "1_1") (pintype "passive"))
      (node (ref "C22") (pin "1") (pinfunction "1_1") (pintype "passive"))
      (node (ref "C23") (pin "2") (pinfunction "2_2") (pintype "passive"))
      (node (ref "C24") (pin "1") (pinfunction "1_1") (pintype "passive"))
      (node (ref "C25") (pin "2") (pinfunction "2_2") (pintype "passive"))
      (node (ref "C26") (pin "2") (pinfunction "2_2") (pintype "passive"))
      (node (ref "C27") (pin "1") (pinfunction "1_1") (pintype "passive"))
      (node (ref "C28") (pin "1") (pinfunction "1_1") (pintype "passive"))
      (node (ref "C29") (pin "1") (pinfunction "1_1") (pintype "passive"))
      (node (ref "C3") (pin "1") (pinfunction "1_1") (pintype "passive"))
      (node (ref "C31") (pin "2") (pinfunction "2_2") (pintype "passive"))
      (node (ref "C33") (pin "1") (pinfunction "1_1") (pintype "passive"))
      (node (ref "C4") (pin "1") (pinfunction "1_1") (pintype "passive"))
      (node (ref "C5") (pin "1") (pinfunction "1_1") (pintype "passive"))
      (node (ref "C6") (pin "2") (pinfunction "2_2") (pintype "passive"))
      (node (ref "C7") (pin "2") (pinfunction "2_2") (pintype "passive"))
      (node (ref "C8") (pin "2") (pinfunction "2_2") (pintype "passive"))
      (node (ref "C9") (pin "2") (pinfunction "2_2") (pintype "passive"))
      (node (ref "CN1") (pin "1") (pinfunction "P$1_1") (pintype "bidirectional"))
      (node (ref "D1") (pin "-") (pinfunction "-_-") (pintype "passive"))
      (node (ref "D2") (pin "-") (pinfunction "-_-") (pintype "passive"))
      (node (ref "D3") (pin "-") (pinfunction "-_-") (pintype "passive"))
      (node (ref "D4") (pin "-") (pinfunction "-_-") (pintype "passive"))
      (node (ref "IC1") (pin "3") (pinfunction "VDD_3") (pintype "bidirectional"))
      (node (ref "IC2") (pin "11") (pinfunction "VSSA_11") (pintype "bidirectional"))
      (node (ref "IC2") (pin "15") (pinfunction "VREFN_15") (pintype "bidirectional"))
      (node (ref "IC2") (pin "16") (pinfunction "RTCX1_16") (pintype "bidirectional"))
      (node (ref "IC2") (pin "31") (pinfunction "VSS_31") (pintype "bidirectional"))
      (node (ref "IC2") (pin "41") (pinfunction "VSS_41") (pintype "bidirectional"))
      (node (ref "IC2") (pin "55") (pinfunction "VSS_55") (pintype "bidirectional"))
      (node (ref "IC2") (pin "72") (pinfunction "VSS_72") (pintype "bidirectional"))
      (node (ref "IC2") (pin "83") (pinfunction "VSS_83") (pintype "bidirectional"))
      (node (ref "IC2") (pin "97") (pinfunction "VSS_97") (pintype "bidirectional"))
      (node (ref "IC3") (pin "1") (pinfunction "GND_1") (pintype "bidirectional"))
      (node (ref "IC4") (pin "3") (pinfunction "VDD_3") (pintype "bidirectional"))
      (node (ref "IC5") (pin "10") (pinfunction "PGND2_10") (pintype "bidirectional"))
      (node (ref "IC5") (pin "18") (pinfunction "GND_18") (pintype "bidirectional"))
      (node (ref "IC5") (pin "3") (pinfunction "PGND_3") (pintype "bidirectional"))
      (node (ref "IC5") (pin "4") (pinfunction "PGND_4") (pintype "bidirectional"))
      (node (ref "IC5") (pin "9") (pinfunction "PGND2_9") (pintype "bidirectional"))
      (node (ref "IC6") (pin "10") (pinfunction "PGND2_10") (pintype "bidirectional"))
      (node (ref "IC6") (pin "18") (pinfunction "GND_18") (pintype "bidirectional"))
      (node (ref "IC6") (pin "3") (pinfunction "PGND_3") (pintype "bidirectional"))
      (node (ref "IC6") (pin "4") (pinfunction "PGND_4") (pintype "bidirectional"))
      (node (ref "IC6") (pin "9") (pinfunction "PGND2_9") (pintype "bidirectional"))
      (node (ref "IC7") (pin "15") (pinfunction "GND_15") (pintype "bidirectional"))
      (node (ref "IR") (pin "3") (pinfunction "GND_3") (pintype "bidirectional"))
      (node (ref "J2") (pin "10") (pinfunction "10_10") (pintype "bidirectional"))
      (node (ref "J2") (pin "11") (pinfunction "11_11") (pintype "bidirectional"))
      (node (ref "J2") (pin "12") (pinfunction "12_12") (pintype "bidirectional"))
      (node (ref "J2") (pin "13") (pinfunction "13_13") (pintype "bidirectional"))
      (node (ref "J2") (pin "14") (pinfunction "14_14") (pintype "bidirectional"))
      (node (ref "J2") (pin "15") (pinfunction "15_15") (pintype "bidirectional"))
      (node (ref "J2") (pin "9") (pinfunction "9_9") (pintype "bidirectional"))
      (node (ref "J3") (pin "5") (pinfunction "GND_5") (pintype "bidirectional"))
      (node (ref "J3") (pin "6") (pinfunction "GND_6") (pintype "bidirectional"))
      (node (ref "J3") (pin "7") (pinfunction "GND_7") (pintype "bidirectional"))
      (node (ref "J4") (pin "3") (pinfunction "3_3") (pintype "bidirectional"))
      (node (ref "J4") (pin "5") (pinfunction "5_5") (pintype "bidirectional"))
      (node (ref "J4") (pin "6") (pinfunction "6_6") (pintype "bidirectional"))
      (node (ref "J4") (pin "G1") (pinfunction "10_G1") (pintype "bidirectional"))
      (node (ref "J4") (pin "G2") (pinfunction "11_G2") (pintype "bidirectional"))
      (node (ref "J5") (pin "10") (pinfunction "10_10") (pintype "bidirectional"))
      (node (ref "J5") (pin "11") (pinfunction "11_11") (pintype "bidirectional"))
      (node (ref "J5") (pin "12") (pinfunction "12_12") (pintype "bidirectional"))
      (node (ref "J5") (pin "13") (pinfunction "13_13") (pintype "bidirectional"))
      (node (ref "J5") (pin "14") (pinfunction "14_14") (pintype "bidirectional"))
      (node (ref "J5") (pin "15") (pinfunction "15_15") (pintype "bidirectional"))
      (node (ref "J5") (pin "9") (pinfunction "9_9") (pintype "bidirectional"))
      (node (ref "J6") (pin "5") (pinfunction "5_5") (pintype "bidirectional"))
      (node (ref "J7") (pin "4") (pinfunction "4_4") (pintype "bidirectional"))
      (node (ref "J8") (pin "16") (pinfunction "16_16") (pintype "bidirectional"))
      (node (ref "J8") (pin "7") (pinfunction "7_7") (pintype "bidirectional"))
      (node (ref "Q2") (pin "2") (pinfunction "S_2") (pintype "passive"))
      (node (ref "SW1") (pin "1") (pinfunction "1_1") (pintype "bidirectional"))
    )
    (net (code "69") (name "Net-(CN1-P$2)") (class "Default")
      (node (ref "CN1") (pin "2") (pinfunction "P$2_2") (pintype "bidirectional"))
      (node (ref "IC2") (pin "6") (pinfunction "P0.26/AD0.3/AOUT/RXD3_6") (pintype "bidirectional"))
    )
    (net (code "70") (name "Net-(CN1-P$3)") (class "Default")
      (node (ref "CN1") (pin "3") (pinfunction "P$3_3") (pintype "bidirectional"))
      (node (ref "IC2") (pin "7") (pinfunction "P0.25/AD0.2/I2SRX_SDA/TXD3_7") (pintype "bidirectional"))
    )
    (net (code "71") (name "Net-(D1-Pad+)") (class "Default")
      (node (ref "D1") (pin "+") (pinfunction "+_+") (pintype "passive"))
      (node (ref "R17") (pin "2") (pinfunction "2_2") (pintype "passive"))
    )
    (net (code "72") (name "Net-(D2-Pad+)") (class "Default")
      (node (ref "D2") (pin "+") (pinfunction "+_+") (pintype "passive"))
      (node (ref "R18") (pin "2") (pinfunction "2_2") (pintype "passive"))
    )
    (net (code "73") (name "Net-(D3-Pad+)") (class "Default")
      (node (ref "D3") (pin "+") (pinfunction "+_+") (pintype "passive"))
      (node (ref "R1") (pin "2") (pinfunction "2_2") (pintype "passive"))
    )
    (net (code "74") (name "Net-(D4-Pad+)") (class "Default")
      (node (ref "D4") (pin "+") (pinfunction "+_+") (pintype "passive"))
      (node (ref "R15") (pin "1") (pinfunction "1_1") (pintype "passive"))
    )
    (net (code "75") (name "Net-(D5-Pad+)") (class "Default")
      (node (ref "D5") (pin "+") (pinfunction "+_+") (pintype "passive"))
      (node (ref "R11") (pin "1") (pinfunction "1_1") (pintype "passive"))
    )
    (net (code "76") (name "Net-(IC2-P0.10{slash}TXD2{slash}SDA2{slash}MAT3.0)") (class "Default")
      (node (ref "IC2") (pin "48") (pinfunction "P0.10/TXD2/SDA2/MAT3.0_48") (pintype "bidirectional"))
      (node (ref "J1") (pin "1") (pinfunction "1_1") (pintype "bidirectional"))
      (node (ref "J2") (pin "1") (pinfunction "1_1") (pintype "bidirectional"))
      (node (ref "J2") (pin "16") (pinfunction "16_16") (pintype "bidirectional"))
    )
    (net (code "77") (name "Net-(IC2-P0.18{slash}DCD1{slash}MOSI0{slash}MOSI1)") (class "Default")
      (node (ref "IC2") (pin "60") (pinfunction "P0.18/DCD1/MOSI0/MOSI1_60") (pintype "bidirectional"))
      (node (ref "R10") (pin "1") (pinfunction "1_1") (pintype "passive"))
    )
    (net (code "78") (name "Net-(IC2-P0.29{slash}USB_D+)") (class "Default")
      (node (ref "C4") (pin "2") (pinfunction "2_2") (pintype "passive"))
      (node (ref "IC2") (pin "29") (pinfunction "P0.29/USB_D+_29") (pintype "bidirectional"))
      (node (ref "R7") (pin "1") (pinfunction "1_1") (pintype "passive"))
    )
    (net (code "79") (name "Net-(IC2-P0.30{slash}USB_D-)") (class "Default")
      (node (ref "C5") (pin "2") (pinfunction "2_2") (pintype "passive"))
      (node (ref "IC2") (pin "30") (pinfunction "P0.30/USB_D-_30") (pintype "bidirectional"))
      (node (ref "R6") (pin "1") (pinfunction "1_1") (pintype "passive"))
    )
    (net (code "80") (name "Net-(IC2-P1.30{slash}VBUS{slash}AD0.4)") (class "Default")
      (node (ref "IC2") (pin "21") (pinfunction "P1.30/VBUS/AD0.4_21") (pintype "bidirectional"))
      (node (ref "R14") (pin "2") (pinfunction "2_2") (pintype "passive"))
    )
    (net (code "81") (name "Net-(IC2-P2.10{slash}EINT0N{slash}NMI)") (class "Default")
      (node (ref "IC2") (pin "53") (pinfunction "P2.10/EINT0N/NMI_53") (pintype "bidirectional"))
      (node (ref "R12") (pin "1") (pinfunction "1_1") (pintype "passive"))
      (node (ref "SW1") (pin "2") (pinfunction "2_2") (pintype "bidirectional"))
    )
    (net (code "82") (name "Net-(IC2-X1)") (class "Default")
      (node (ref "C14") (pin "2") (pinfunction "2_2") (pintype "passive"))
      (node (ref "IC2") (pin "22") (pinfunction "X1_22") (pintype "bidirectional"))
      (node (ref "Y1") (pin "1") (pinfunction "1_1") (pintype "passive"))
    )
    (net (code "83") (name "Net-(IC2-X2)") (class "Default")
      (node (ref "C13") (pin "2") (pinfunction "2_2") (pintype "passive"))
      (node (ref "IC2") (pin "23") (pinfunction "X2_23") (pintype "bidirectional"))
      (node (ref "Y1") (pin "2") (pinfunction "2_2") (pintype "passive"))
    )
    (net (code "84") (name "Net-(IC7-C1+)") (class "Default")
      (node (ref "C32") (pin "1") (pinfunction "1_1") (pintype "passive"))
      (node (ref "IC7") (pin "1") (pinfunction "C1+_1") (pintype "bidirectional"))
    )
    (net (code "85") (name "Net-(IC7-C1-)") (class "Default")
      (node (ref "C32") (pin "2") (pinfunction "2_2") (pintype "passive"))
      (node (ref "IC7") (pin "3") (pinfunction "C1-_3") (pintype "bidirectional"))
    )
    (net (code "86") (name "Net-(IC7-C2+)") (class "Default")
      (node (ref "C30") (pin "2") (pinfunction "2_2") (pintype "passive"))
      (node (ref "IC7") (pin "4") (pinfunction "C2+_4") (pintype "bidirectional"))
    )
    (net (code "87") (name "Net-(IC7-C2-)") (class "Default")
      (node (ref "C30") (pin "1") (pinfunction "1_1") (pintype "passive"))
      (node (ref "IC7") (pin "5") (pinfunction "C2-_5") (pintype "bidirectional"))
    )
    (net (code "88") (name "Net-(IC7-V+)") (class "Default")
      (node (ref "C31") (pin "1") (pinfunction "1_1") (pintype "passive"))
      (node (ref "IC7") (pin "2") (pinfunction "V+_2") (pintype "bidirectional"))
    )
    (net (code "89") (name "Net-(IC7-V-)") (class "Default")
      (node (ref "C29") (pin "2") (pinfunction "2_2") (pintype "passive"))
      (node (ref "IC7") (pin "6") (pinfunction "V-_6") (pintype "bidirectional"))
    )
    (net (code "90") (name "Net-(J3-DM)") (class "Default")
      (node (ref "J3") (pin "2") (pinfunction "DM_2") (pintype "bidirectional"))
      (node (ref "R6") (pin "2") (pinfunction "2_2") (pintype "passive"))
    )
    (net (code "91") (name "Net-(J3-DP)") (class "Default")
      (node (ref "J3") (pin "3") (pinfunction "DP_3") (pintype "bidirectional"))
      (node (ref "R7") (pin "2") (pinfunction "2_2") (pintype "passive"))
      (node (ref "R8") (pin "1") (pinfunction "1_1") (pintype "passive"))
    )
    (net (code "92") (name "Net-(J9-Pad1)") (class "Default")
      (node (ref "J9") (pin "1") (pinfunction "1_1") (pintype "bidirectional"))
      (node (ref "R13") (pin "1") (pinfunction "1_1") (pintype "passive"))
    )
    (net (code "93") (name "Net-(J10-Pad1)") (class "Default")
      (node (ref "J10") (pin "1") (pinfunction "1_1") (pintype "bidirectional"))
      (node (ref "R9") (pin "1") (pinfunction "1_1") (pintype "passive"))
    )
    (net (code "94") (name "Net-(Q1-B)") (class "Default")
      (node (ref "Q1") (pin "1") (pinfunction "B_1") (pintype "passive"))
      (node (ref "R5") (pin "2") (pinfunction "2_2") (pintype "passive"))
    )
    (net (code "95") (name "Net-(Q1-C)") (class "Default")
      (node (ref "Q1") (pin "3") (pinfunction "C_3") (pintype "passive"))
      (node (ref "R8") (pin "2") (pinfunction "2_2") (pintype "passive"))
    )
    (net (code "96") (name "Net-(Q2-D)") (class "Default")
      (node (ref "D5") (pin "-") (pinfunction "-_-") (pintype "passive"))
      (node (ref "Q2") (pin "3") (pinfunction "D_3") (pintype "passive"))
    )
    (net (code "97") (name "VCC") (class "Default")
      (node (ref "C15") (pin "2") (pinfunction "2_2") (pintype "passive"))
      (node (ref "C33") (pin "2") (pinfunction "2_2") (pintype "passive"))
      (node (ref "C6") (pin "1") (pinfunction "1_1") (pintype "passive"))
      (node (ref "C7") (pin "1") (pinfunction "1_1") (pintype "passive"))
      (node (ref "C8") (pin "1") (pinfunction "1_1") (pintype "passive"))
      (node (ref "IC1") (pin "2") (pinfunction "VSS_2") (pintype "bidirectional"))
      (node (ref "IC3") (pin "3") (pinfunction "IN_3") (pintype "bidirectional"))
      (node (ref "IC4") (pin "2") (pinfunction "VSS_2") (pintype "bidirectional"))
      (node (ref "IC7") (pin "16") (pinfunction "VCC_16") (pintype "bidirectional"))
      (node (ref "J3") (pin "1") (pinfunction "VCC_1") (pintype "bidirectional"))
      (node (ref "J8") (pin "6") (pinfunction "6_6") (pintype "bidirectional"))
      (node (ref "R11") (pin "2") (pinfunction "2_2") (pintype "passive"))
      (node (ref "R14") (pin "1") (pinfunction "1_1") (pintype "passive"))
    )
    (net (code "98") (name "VDD") (class "Default")
      (node (ref "C1") (pin "2") (pinfunction "2_2") (pintype "passive"))
      (node (ref "C10") (pin "1") (pinfunction "1_1") (pintype "passive"))
      (node (ref "C11") (pin "2") (pinfunction "2_2") (pintype "passive"))
      (node (ref "C12") (pin "2") (pinfunction "2_2") (pintype "passive"))
      (node (ref "C18") (pin "2") (pinfunction "2_2") (pintype "passive"))
      (node (ref "C19") (pin "2") (pinfunction "2_2") (pintype "passive"))
      (node (ref "C2") (pin "2") (pinfunction "2_2") (pintype "passive"))
      (node (ref "C20") (pin "2") (pinfunction "2_2") (pintype "passive"))
      (node (ref "C21") (pin "2") (pinfunction "2_2") (pintype "passive"))
      (node (ref "C22") (pin "2") (pinfunction "2_2") (pintype "passive"))
      (node (ref "C25") (pin "1") (pinfunction "1_1") (pintype "passive"))
      (node (ref "C26") (pin "1") (pinfunction "1_1") (pintype "passive"))
      (node (ref "C27") (pin "2") (pinfunction "2_2") (pintype "passive"))
      (node (ref "C28") (pin "2") (pinfunction "2_2") (pintype "passive"))
      (node (ref "C3") (pin "2") (pinfunction "2_2") (pintype "passive"))
      (node (ref "C9") (pin "1") (pinfunction "1_1") (pintype "passive"))
      (node (ref "IC2") (pin "10") (pinfunction "VDDA_10") (pintype "bidirectional"))
      (node (ref "IC2") (pin "12") (pinfunction "VREFP_12") (pintype "bidirectional"))
      (node (ref "IC2") (pin "19") (pinfunction "VBAT_19") (pintype "bidirectional"))
      (node (ref "IC2") (pin "28") (pinfunction "VDD3.3V_28") (pintype "bidirectional"))
      (node (ref "IC2") (pin "42") (pinfunction "VDDREG3.3V_42") (pintype "bidirectional"))
      (node (ref "IC2") (pin "54") (pinfunction "VDD3.3V_54") (pintype "bidirectional"))
      (node (ref "IC2") (pin "71") (pinfunction "VDD3.3V_71") (pintype "bidirectional"))
      (node (ref "IC2") (pin "84") (pinfunction "VDDREG3.3V_84") (pintype "bidirectional"))
      (node (ref "IC2") (pin "96") (pinfunction "VDD3.3V_96") (pintype "bidirectional"))
      (node (ref "IC3") (pin "2") (pinfunction "OUT_2") (pintype "bidirectional"))
      (node (ref "IC3") (pin "TER") (pinfunction "OUT_TER") (pintype "bidirectional"))
      (node (ref "IC5") (pin "20") (pinfunction "VCC_20") (pintype "bidirectional"))
      (node (ref "IC6") (pin "20") (pinfunction "VCC_20") (pintype "bidirectional"))
      (node (ref "IR") (pin "2") (pinfunction "VS_2") (pintype "bidirectional"))
      (node (ref "J5") (pin "1") (pinfunction "1_1") (pintype "bidirectional"))
      (node (ref "J5") (pin "16") (pinfunction "16_16") (pintype "bidirectional"))
      (node (ref "J7") (pin "6") (pinfunction "6_6") (pintype "bidirectional"))
      (node (ref "J7") (pin "8") (pinfunction "8_8") (pintype "bidirectional"))
      (node (ref "J8") (pin "10") (pinfunction "10_10") (pintype "bidirectional"))
      (node (ref "Q1") (pin "2") (pinfunction "E_2") (pintype "passive"))
      (node (ref "R12") (pin "2") (pinfunction "2_2") (pintype "passive"))
      (node (ref "R15") (pin "2") (pinfunction "2_2") (pintype "passive"))
      (node (ref "R16") (pin "2") (pinfunction "2_2") (pintype "passive"))
    )
    (net (code "99") (name "unconnected-(IC2-NC-Pad13)") (class "Default")
      (node (ref "IC2") (pin "13") (pinfunction "NC_13") (pintype "bidirectional"))
    )
    (net (code "100") (name "unconnected-(IC2-P0.7{slash}I2STX_CLK{slash}SCK1{slash}MAT2.1-Pad78)") (class "Default")
      (node (ref "IC2") (pin "78") (pinfunction "P0.7/I2STX_CLK/SCK1/MAT2.1_78") (pintype "bidirectional"))
    )
    (net (code "101") (name "unconnected-(IC2-P0.19{slash}DSR1{slash}MCICLK{slash}SDA1-Pad59)") (class "Default")
      (node (ref "IC2") (pin "59") (pinfunction "P0.19/DSR1/MCICLK/SDA1_59") (pintype "bidirectional"))
    )
    (net (code "102") (name "unconnected-(IC2-P0.27{slash}SDA0{slash}USB_SDA-Pad25)") (class "Default")
      (node (ref "IC2") (pin "25") (pinfunction "P0.27/SDA0/USB_SDA_25") (pintype "bidirectional"))
    )
    (net (code "103") (name "unconnected-(IC2-P0.28{slash}SCL0{slash}USB_SCL-Pad24)") (class "Default")
      (node (ref "IC2") (pin "24") (pinfunction "P0.28/SCL0/USB_SCL_24") (pintype "bidirectional"))
    )
    (net (code "104") (name "unconnected-(IC2-P1.15{slash}ENET-RX_CLK-Pad88)") (class "Default")
      (node (ref "IC2") (pin "88") (pinfunction "P1.15/ENET-RX_CLK_88") (pintype "bidirectional"))
    )
    (net (code "105") (name "unconnected-(IC2-P1.16{slash}ENET-MDC-Pad87)") (class "Default")
      (node (ref "IC2") (pin "87") (pinfunction "P1.16/ENET-MDC_87") (pintype "bidirectional"))
    )
    (net (code "106") (name "unconnected-(IC2-P1.17{slash}ENET-MDIO-Pad86)") (class "Default")
      (node (ref "IC2") (pin "86") (pinfunction "P1.17/ENET-MDIO_86") (pintype "bidirectional"))
    )
    (net (code "107") (name "unconnected-(IC2-P1.19{slash}MC0A{slash}USB_PPWR{slash}CAP1.1-Pad33)") (class "Default")
      (node (ref "IC2") (pin "33") (pinfunction "P1.19/MC0A/USB_PPWR/CAP1.1_33") (pintype "bidirectional"))
    )
    (net (code "108") (name "unconnected-(IC2-P1.20{slash}MCFB0{slash}PWM1.2{slash}SCK0-Pad34)") (class "Default")
      (node (ref "IC2") (pin "34") (pinfunction "P1.20/MCFB0/PWM1.2/SCK0_34") (pintype "bidirectional"))
    )
    (net (code "109") (name "unconnected-(IC2-P1.22{slash}MC0B{slash}USB_PWRD{slash}MAT1.0-Pad36)") (class "Default")
      (node (ref "IC2") (pin "36") (pinfunction "P1.22/MC0B/USB_PWRD/MAT1.0_36") (pintype "bidirectional"))
    )
    (net (code "110") (name "unconnected-(IC2-P1.24{slash}MCFB2{slash}PWM1.5{slash}MOSI0-Pad38)") (class "Default")
      (node (ref "IC2") (pin "38") (pinfunction "P1.24/MCFB2/PWM1.5/MOSI0_38") (pintype "bidirectional"))
    )
    (net (code "111") (name "unconnected-(IC2-P1.25{slash}MC1A{slash}MAT1.1-Pad39)") (class "Default")
      (node (ref "IC2") (pin "39") (pinfunction "P1.25/MC1A/MAT1.1_39") (pintype "bidirectional"))
    )
    (net (code "112") (name "unconnected-(IC2-P1.28{slash}MC2A{slash}PCAP1.0{slash}MAT0.0-Pad44)") (class "Default")
      (node (ref "IC2") (pin "44") (pinfunction "P1.28/MC2A/PCAP1.0/MAT0.0_44") (pintype "bidirectional"))
    )
    (net (code "113") (name "unconnected-(IC2-P1.29{slash}MC2B{slash}PCAP1.1{slash}MAT0.1-Pad45)") (class "Default")
      (node (ref "IC2") (pin "45") (pinfunction "P1.29/MC2B/PCAP1.1/MAT0.1_45") (pintype "bidirectional"))
    )
    (net (code "114") (name "unconnected-(IC2-P1.31{slash}SCK1{slash}AD0.5-Pad20)") (class "Default")
      (node (ref "IC2") (pin "20") (pinfunction "P1.31/SCK1/AD0.5_20") (pintype "bidirectional"))
    )
    (net (code "115") (name "unconnected-(IC2-P2.2{slash}PWM1.3{slash}CTS1{slash}TRACEDATA3-Pad73)") (class "Default")
      (node (ref "IC2") (pin "73") (pinfunction "P2.2/PWM1.3/CTS1/TRACEDATA3_73") (pintype "bidirectional"))
    )
    (net (code "116") (name "unconnected-(IC2-P2.11{slash}EINT1N{slash}I2STX_CLK-Pad52)") (class "Default")
      (node (ref "IC2") (pin "52") (pinfunction "P2.11/EINT1N/I2STX_CLK_52") (pintype "bidirectional"))
    )
    (net (code "117") (name "unconnected-(IC2-P2.12{slash}EINT2N{slash}I2STX_WS-Pad51)") (class "Default")
      (node (ref "IC2") (pin "51") (pinfunction "P2.12/EINT2N/I2STX_WS_51") (pintype "bidirectional"))
    )
    (net (code "118") (name "unconnected-(IC2-P2.13{slash}EINT3N{slash}I2STX_SDA-Pad50)") (class "Default")
      (node (ref "IC2") (pin "50") (pinfunction "P2.13/EINT3N/I2STX_SDA_50") (pintype "bidirectional"))
    )
    (net (code "119") (name "unconnected-(IC2-RSTOUTN-Pad14)") (class "Default")
      (node (ref "IC2") (pin "14") (pinfunction "RSTOUTN_14") (pintype "bidirectional"))
    )
    (net (code "120") (name "unconnected-(IC2-RTCX2-Pad18)") (class "Default")
      (node (ref "IC2") (pin "18") (pinfunction "RTCX2_18") (pintype "bidirectional"))
    )
    (net (code "121") (name "unconnected-(J3-ID-Pad4)") (class "Default")
      (node (ref "J3") (pin "4") (pinfunction "ID_4") (pintype "bidirectional"))
    )
    (net (code "122") (name "unconnected-(J4-Pad4)") (class "Default")
      (node (ref "J4") (pin "4") (pinfunction "4_4") (pintype "bidirectional"))
    )
    (net (code "123") (name "unconnected-(J4-Pad9)") (class "Default")
      (node (ref "J4") (pin "9") (pinfunction "9_9") (pintype "bidirectional"))
    )
    (net (code "124") (name "unconnected-(J6-10-PadG1)") (class "Default")
      (node (ref "J6") (pin "G1") (pinfunction "10_G1") (pintype "bidirectional"))
    )
    (net (code "125") (name "unconnected-(J6-11-PadG2)") (class "Default")
      (node (ref "J6") (pin "G2") (pinfunction "11_G2") (pintype "bidirectional"))
    )
    (net (code "126") (name "unconnected-(J6-Pad4)") (class "Default")
      (node (ref "J6") (pin "4") (pinfunction "4_4") (pintype "bidirectional"))
    )
    (net (code "127") (name "unconnected-(J6-Pad7)") (class "Default")
      (node (ref "J6") (pin "7") (pinfunction "7_7") (pintype "bidirectional"))
    )
    (net (code "128") (name "unconnected-(J6-Pad8)") (class "Default")
      (node (ref "J6") (pin "8") (pinfunction "8_8") (pintype "bidirectional"))
    )
    (net (code "129") (name "unconnected-(J6-Pad9)") (class "Default")
      (node (ref "J6") (pin "9") (pinfunction "9_9") (pintype "bidirectional"))
    )
  )
)
